# TempControl_V2_0.net
KiCad netlist of a schematic drawn in EAGLE
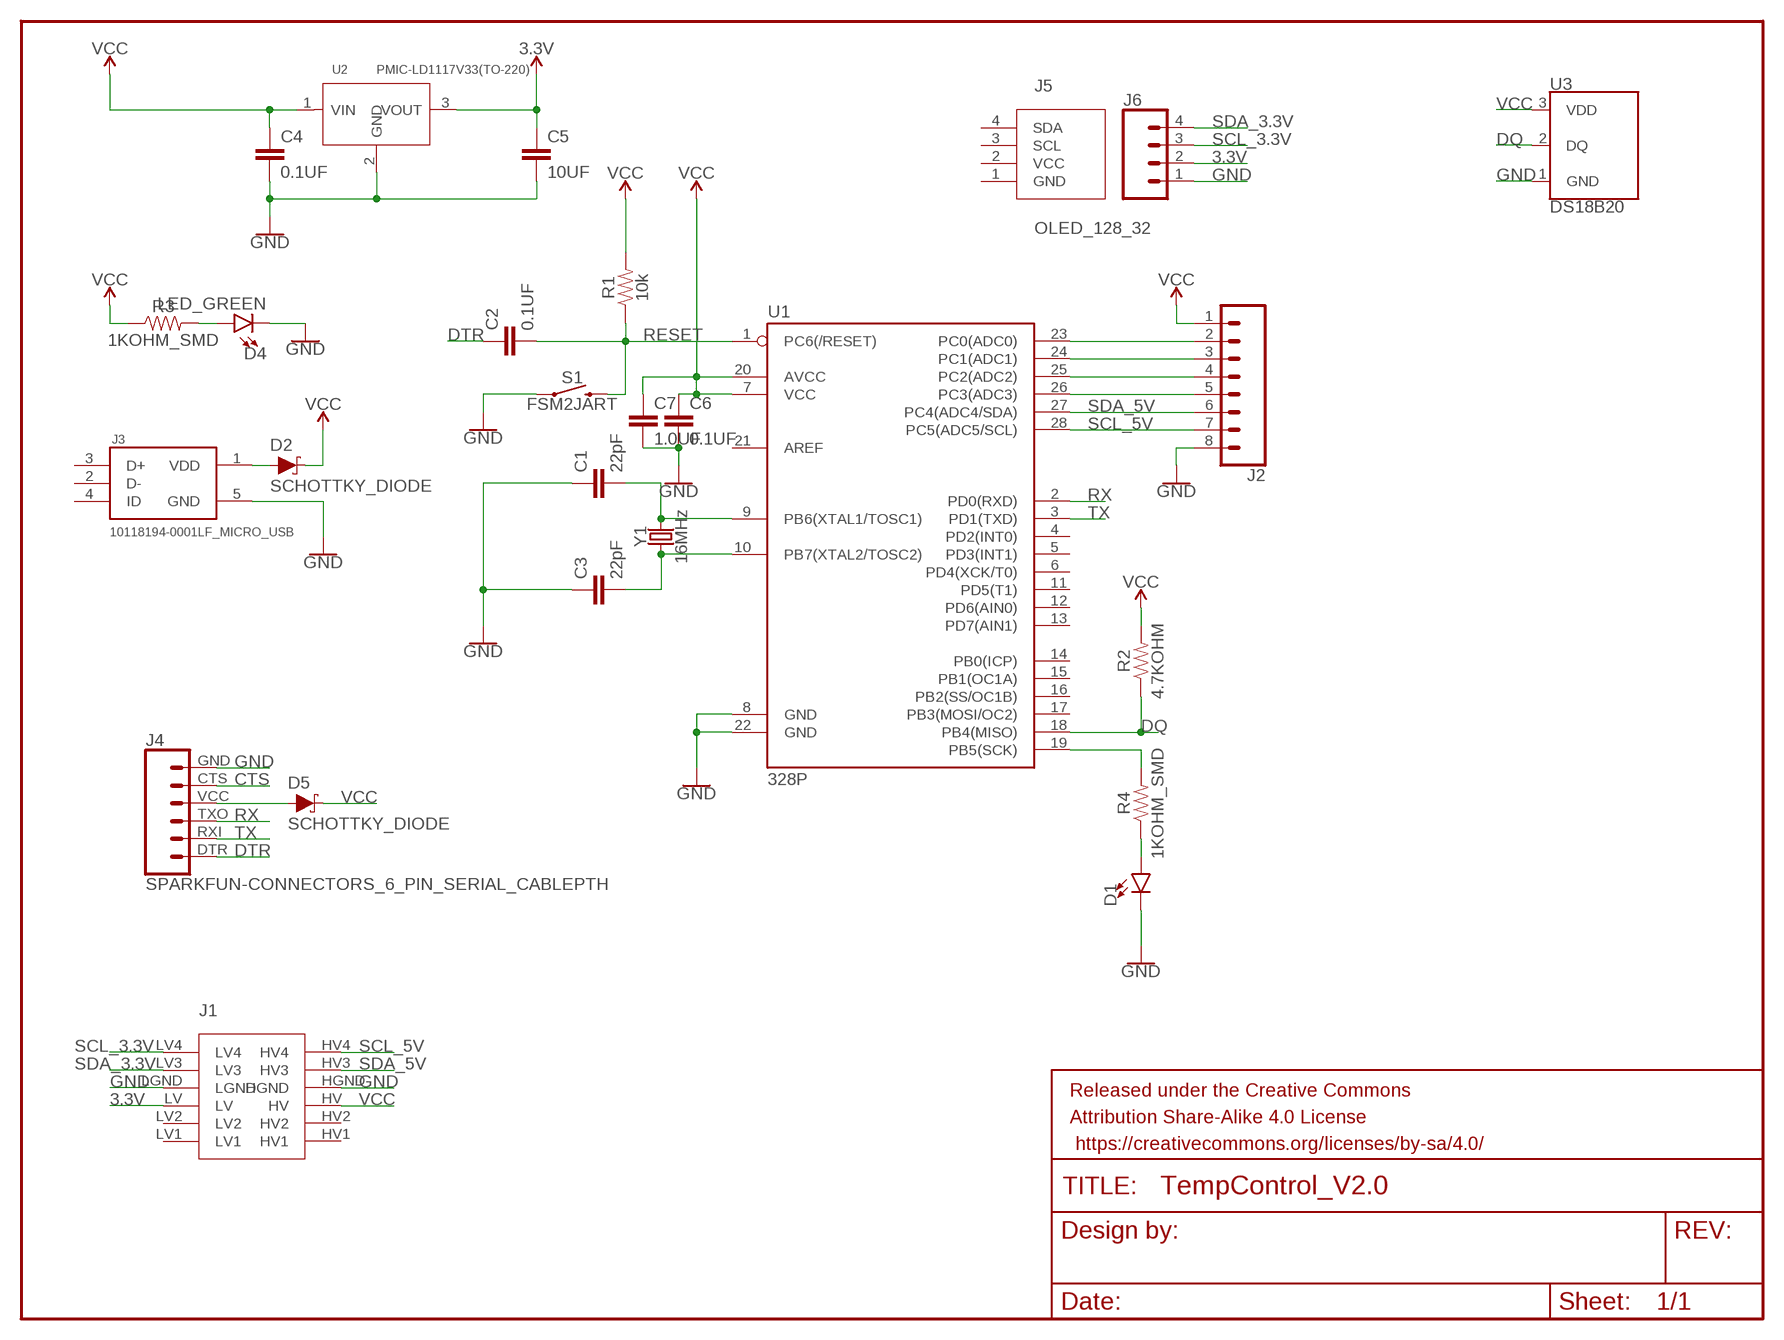
[diagram p0: schematic, sheet 1]

(export (version "E")
  (design (tool "Eeschema 10.0.6"))
  (components
    (comp (ref "C1")
      (value "22pF")
      (footprint "eagle-import:CAP-PTH-2.54")
      (libsource (lib "eagle-import") (part "22PF-PTH-2.54MM-200V-5%"))
    )
    (comp (ref "C2")
      (value "0.1UF")
      (footprint "eagle-import:CAP-PTH-2.54")
      (libsource (lib "eagle-import") (part "0.1UF"))
    )
    (comp (ref "C3")
      (value "22pF")
      (footprint "eagle-import:CAP-PTH-2.54")
      (libsource (lib "eagle-import") (part "22PF-PTH-2.54MM-200V-5%"))
    )
    (comp (ref "C4")
      (value "0.1UF")
      (footprint "eagle-import:CAP-PTH-2.54")
      (libsource (lib "eagle-import") (part "0.1UF"))
    )
    (comp (ref "C5")
      (value "10UF")
      (footprint "eagle-import:CAP-PTH-5MM")
      (libsource (lib "eagle-import") (part "10UF"))
    )
    (comp (ref "C6")
      (value "0.1UF")
      (footprint "eagle-import:CAP-PTH-2.54")
      (libsource (lib "eagle-import") (part "0.1UF"))
    )
    (comp (ref "C7")
      (value "1.0UF")
      (footprint "eagle-import:CAP-PTH-5MM")
      (libsource (lib "eagle-import") (part "1.0UF"))
    )
    (comp (ref "D1")
      (value "LED_RED5MM")
      (footprint "eagle-import:LED_5MM")
      (libsource (lib "eagle-import") (part "LED_RED5MM"))
    )
    (comp (ref "D2")
      (value "SCHOTTKY_DIODE")
      (footprint "eagle-import:DIODE_0805")
      (libsource (lib "eagle-import") (part "SCHOTTKY_DIODE"))
    )
    (comp (ref "D4")
      (value "LED_GREEN")
      (footprint "eagle-import:LED-0603")
      (libsource (lib "eagle-import") (part "LED_GREEN"))
    )
    (comp (ref "D5")
      (value "SCHOTTKY_DIODE")
      (footprint "eagle-import:DIODE_0805")
      (libsource (lib "eagle-import") (part "SCHOTTKY_DIODE"))
    )
    (comp (ref "FRAME1")
      (value "FRAME-LETTERNO_PACKAGE")
      (footprint "eagle-import:DUMMY")
      (fields (field (name "DESIGNER") "Nobody"))
      (libsource (lib "eagle-import") (part "FRAME-LETTERNO_PACKAGE"))
    )
    (comp (ref "J1")
      (value "LEVEL_SHIFTER")
      (footprint "eagle-import:LEVEL_SHIFTER")
      (libsource (lib "eagle-import") (part "LEVEL_SHIFTER"))
    )
    (comp (ref "J2")
      (value "SPARKFUN-CONNECTORS_CONN_08\"")
      (footprint "eagle-import:SPARKFUN-CONNECTORS_1X08")
      (libsource (lib "eagle-import") (part "SPARKFUN-CONNECTORS_CONN_08{dblquote}"))
    )
    (comp (ref "J3")
      (value "10118194-0001LF_MICRO_USB")
      (footprint "eagle-import:FRAMATOME_10118194-0001LF")
      (fields (field (name "MF") "Amphenol") (field (name "MP") "10118194-0001LF"))
      (libsource (lib "eagle-import") (part "10118194-0001LF_MICRO_USB"))
    )
    (comp (ref "J4")
      (value "SPARKFUN-CONNECTORS_6_PIN_SERIAL_CABLEPTH")
      (footprint "eagle-import:SPARKFUN-CONNECTORS_FTDI_BASIC")
      (libsource (lib "eagle-import") (part "SPARKFUN-CONNECTORS_6_PIN_SERIAL_CABLEPTH"))
    )
    (comp (ref "J5")
      (value "OLED_128_32")
      (footprint "eagle-import:OLED_128_32")
      (libsource (lib "eagle-import") (part "OLED_128_32"))
    )
    (comp (ref "J6")
      (value "CONN_04")
      (footprint "eagle-import:1X04")
      (libsource (lib "eagle-import") (part "CONN_04"))
    )
    (comp (ref "R1")
      (value "10k")
      (footprint "eagle-import:AXIAL-0.3")
      (libsource (lib "eagle-import") (part "10KOHM-HORIZ-1/4W-1%"))
    )
    (comp (ref "R2")
      (value "4.7KOHM")
      (footprint "eagle-import:AXIAL-0.3")
      (libsource (lib "eagle-import") (part "4.7KOHM"))
    )
    (comp (ref "R3")
      (value "1KOHM_SMD")
      (footprint "eagle-import:0603")
      (libsource (lib "eagle-import") (part "1KOHM_SMD"))
    )
    (comp (ref "R4")
      (value "1KOHM_SMD")
      (footprint "eagle-import:0603")
      (libsource (lib "eagle-import") (part "1KOHM_SMD"))
    )
    (comp (ref "S1")
      (value "FSM2JART")
      (footprint "eagle-import:FSM2JART")
      (libsource (lib "eagle-import") (part "FSM2JART"))
    )
    (comp (ref "U1")
      (value "328P")
      (footprint "eagle-import:DIP28")
      (libsource (lib "eagle-import") (part "ATMEGA328P_PDIP"))
    )
    (comp (ref "U2")
      (value "PMIC-LD1117V33(TO-220)")
      (footprint "eagle-import:TO-220")
      (fields (field (name "MF") "STMicroelectronics") (field (name "MP") "LD1117V33"))
      (libsource (lib "eagle-import") (part "PMIC-LD1117V33(TO-220)"))
    )
    (comp (ref "U3")
      (value "DS18B20")
      (footprint "eagle-import:TO-92-AMMO")
      (libsource (lib "eagle-import") (part "DS18B20"))
    )
    (comp (ref "Y1")
      (value "16MHz")
      (footprint "eagle-import:HC49US")
      (libsource (lib "eagle-import") (part "CRYSTAL-16MHZPTH-HC49US"))
    )
  )
  (nets
    (net (code "1") (name "/CTS") (class "Default")
      (node (ref "J4") (pin "CTS") (pinfunction "5_CTS") (pintype "passive"))
    )
    (net (code "2") (name "/DQ") (class "Default")
      (node (ref "R2") (pin "P$1") (pinfunction "1_P$1") (pintype "passive"))
      (node (ref "U1") (pin "18") (pinfunction "PB4(MISO)_18") (pintype "bidirectional"))
      (node (ref "U3") (pin "2") (pinfunction "DQ_2") (pintype "bidirectional"))
    )
    (net (code "3") (name "/DTR") (class "Default")
      (node (ref "C2") (pin "1") (pinfunction "1_1") (pintype "passive"))
      (node (ref "J4") (pin "DTR") (pinfunction "1_DTR") (pintype "passive"))
    )
    (net (code "4") (name "/RESET") (class "Default")
      (node (ref "C2") (pin "2") (pinfunction "2_2") (pintype "passive"))
      (node (ref "R1") (pin "P$1") (pinfunction "1_P$1") (pintype "passive"))
      (node (ref "S1") (pin "2") (pinfunction "2_2") (pintype "passive"))
      (node (ref "U1") (pin "1") (pinfunction "PC6(/RESET)_1") (pintype "bidirectional"))
    )
    (net (code "5") (name "/RX") (class "Default")
      (node (ref "J4") (pin "TXO") (pinfunction "3_TXO") (pintype "passive"))
      (node (ref "U1") (pin "2") (pinfunction "PD0(RXD)_2") (pintype "bidirectional"))
    )
    (net (code "6") (name "/SCL_3.3V") (class "Default")
      (node (ref "J1") (pin "LV4") (pinfunction "LV4_LV4") (pintype "bidirectional"))
      (node (ref "J6") (pin "3") (pinfunction "3_3") (pintype "passive"))
    )
    (net (code "7") (name "/SCL_5V") (class "Default")
      (node (ref "J1") (pin "HV4") (pinfunction "HV4_HV4") (pintype "bidirectional"))
      (node (ref "J2") (pin "7") (pinfunction "7_7") (pintype "passive"))
      (node (ref "U1") (pin "28") (pinfunction "PC5(ADC5/SCL)_28") (pintype "bidirectional"))
    )
    (net (code "8") (name "/SDA_3.3V") (class "Default")
      (node (ref "J1") (pin "LV3") (pinfunction "LV3_LV3") (pintype "bidirectional"))
      (node (ref "J6") (pin "4") (pinfunction "4_4") (pintype "passive"))
    )
    (net (code "9") (name "/SDA_5V") (class "Default")
      (node (ref "J1") (pin "HV3") (pinfunction "HV3_HV3") (pintype "bidirectional"))
      (node (ref "J2") (pin "6") (pinfunction "6_6") (pintype "passive"))
      (node (ref "U1") (pin "27") (pinfunction "PC4(ADC4/SDA)_27") (pintype "bidirectional"))
    )
    (net (code "10") (name "/TX") (class "Default")
      (node (ref "J4") (pin "RXI") (pinfunction "2_RXI") (pintype "passive"))
      (node (ref "U1") (pin "3") (pinfunction "PD1(TXD)_3") (pintype "bidirectional"))
    )
    (net (code "11") (name "3.3V") (class "Default")
      (node (ref "C5") (pin "1") (pinfunction "1_1") (pintype "passive"))
      (node (ref "J1") (pin "LV") (pinfunction "LV_LV") (pintype "bidirectional"))
      (node (ref "J6") (pin "2") (pinfunction "2_2") (pintype "passive"))
      (node (ref "U2") (pin "3") (pinfunction "VOUT_3") (pintype "bidirectional"))
    )
    (net (code "12") (name "GND") (class "Default")
      (node (ref "C1") (pin "1") (pinfunction "1_1") (pintype "passive"))
      (node (ref "C3") (pin "1") (pinfunction "1_1") (pintype "passive"))
      (node (ref "C4") (pin "2") (pinfunction "2_2") (pintype "passive"))
      (node (ref "C5") (pin "2") (pinfunction "2_2") (pintype "passive"))
      (node (ref "C6") (pin "2") (pinfunction "2_2") (pintype "passive"))
      (node (ref "C7") (pin "2") (pinfunction "2_2") (pintype "passive"))
      (node (ref "D1") (pin "K") (pinfunction "2_K") (pintype "passive"))
      (node (ref "D4") (pin "2") (pinfunction "2_2") (pintype "passive"))
      (node (ref "J1") (pin "HGND") (pinfunction "HGND_HGND") (pintype "bidirectional"))
      (node (ref "J1") (pin "LGND") (pinfunction "LGND_LGND") (pintype "bidirectional"))
      (node (ref "J2") (pin "8") (pinfunction "8_8") (pintype "passive"))
      (node (ref "J3") (pin "5") (pinfunction "GND_5") (pintype "power_in"))
      (node (ref "J4") (pin "GND") (pinfunction "6_GND") (pintype "passive"))
      (node (ref "J6") (pin "1") (pinfunction "1_1") (pintype "passive"))
      (node (ref "S1") (pin "1") (pinfunction "1_1") (pintype "passive"))
      (node (ref "U1") (pin "22") (pinfunction "GND_22") (pintype "bidirectional"))
      (node (ref "U1") (pin "8") (pinfunction "GND_8") (pintype "bidirectional"))
      (node (ref "U2") (pin "2") (pinfunction "GND_2") (pintype "bidirectional"))
      (node (ref "U3") (pin "1") (pinfunction "GND_1") (pintype "power_in"))
    )
    (net (code "13") (name "Net-(D1-1)") (class "Default")
      (node (ref "D1") (pin "A") (pinfunction "1_A") (pintype "passive"))
      (node (ref "R4") (pin "1") (pinfunction "1_1") (pintype "passive"))
    )
    (net (code "14") (name "Net-(D4-Pad1)") (class "Default")
      (node (ref "D4") (pin "1") (pinfunction "1_1") (pintype "passive"))
      (node (ref "R3") (pin "2") (pinfunction "2_2") (pintype "passive"))
    )
    (net (code "15") (name "Net-(J3-VDD)") (class "Default")
      (node (ref "D2") (pin "1") (pinfunction "1_1") (pintype "passive"))
      (node (ref "J3") (pin "1") (pinfunction "VDD_1") (pintype "power_in"))
    )
    (net (code "16") (name "Net-(J4-4)") (class "Default")
      (node (ref "D5") (pin "1") (pinfunction "1_1") (pintype "passive"))
      (node (ref "J4") (pin "VCC") (pinfunction "4_VCC") (pintype "passive"))
    )
    (net (code "17") (name "Net-(U1-PB5(SCK))") (class "Default")
      (node (ref "R4") (pin "2") (pinfunction "2_2") (pintype "passive"))
      (node (ref "U1") (pin "19") (pinfunction "PB5(SCK)_19") (pintype "bidirectional"))
    )
    (net (code "18") (name "Net-(U1-PB6(XTAL1{slash}TOSC1))") (class "Default")
      (node (ref "C1") (pin "2") (pinfunction "2_2") (pintype "passive"))
      (node (ref "U1") (pin "9") (pinfunction "PB6(XTAL1/TOSC1)_9") (pintype "bidirectional"))
      (node (ref "Y1") (pin "2") (pinfunction "2_2") (pintype "passive"))
    )
    (net (code "19") (name "Net-(U1-PB7(XTAL2{slash}TOSC2))") (class "Default")
      (node (ref "C3") (pin "2") (pinfunction "2_2") (pintype "passive"))
      (node (ref "U1") (pin "10") (pinfunction "PB7(XTAL2/TOSC2)_10") (pintype "bidirectional"))
      (node (ref "Y1") (pin "1") (pinfunction "1_1") (pintype "passive"))
    )
    (net (code "20") (name "Net-(U1-PC0(ADC0))") (class "Default")
      (node (ref "J2") (pin "2") (pinfunction "2_2") (pintype "passive"))
      (node (ref "U1") (pin "23") (pinfunction "PC0(ADC0)_23") (pintype "bidirectional"))
    )
    (net (code "21") (name "Net-(U1-PC1(ADC1))") (class "Default")
      (node (ref "J2") (pin "3") (pinfunction "3_3") (pintype "passive"))
      (node (ref "U1") (pin "24") (pinfunction "PC1(ADC1)_24") (pintype "bidirectional"))
    )
    (net (code "22") (name "Net-(U1-PC2(ADC2))") (class "Default")
      (node (ref "J2") (pin "4") (pinfunction "4_4") (pintype "passive"))
      (node (ref "U1") (pin "25") (pinfunction "PC2(ADC2)_25") (pintype "bidirectional"))
    )
    (net (code "23") (name "Net-(U1-PC3(ADC3))") (class "Default")
      (node (ref "J2") (pin "5") (pinfunction "5_5") (pintype "passive"))
      (node (ref "U1") (pin "26") (pinfunction "PC3(ADC3)_26") (pintype "bidirectional"))
    )
    (net (code "24") (name "VCC") (class "Default")
      (node (ref "C4") (pin "1") (pinfunction "1_1") (pintype "passive"))
      (node (ref "C6") (pin "1") (pinfunction "1_1") (pintype "passive"))
      (node (ref "C7") (pin "1") (pinfunction "1_1") (pintype "passive"))
      (node (ref "D2") (pin "2") (pinfunction "2_2") (pintype "passive"))
      (node (ref "D5") (pin "2") (pinfunction "2_2") (pintype "passive"))
      (node (ref "J1") (pin "HV") (pinfunction "HV_HV") (pintype "bidirectional"))
      (node (ref "J2") (pin "1") (pinfunction "1_1") (pintype "passive"))
      (node (ref "R1") (pin "P$2") (pinfunction "2_P$2") (pintype "passive"))
      (node (ref "R2") (pin "P$2") (pinfunction "2_P$2") (pintype "passive"))
      (node (ref "R3") (pin "1") (pinfunction "1_1") (pintype "passive"))
      (node (ref "U1") (pin "20") (pinfunction "AVCC_20") (pintype "bidirectional"))
      (node (ref "U1") (pin "7") (pinfunction "VCC_7") (pintype "bidirectional"))
      (node (ref "U2") (pin "1") (pinfunction "VIN_1") (pintype "bidirectional"))
      (node (ref "U3") (pin "3") (pinfunction "VDD_3") (pintype "power_in"))
    )
    (net (code "25") (name "unconnected-(J1-PadHV1)") (class "Default")
      (node (ref "J1") (pin "HV1") (pinfunction "HV1_HV1") (pintype "bidirectional"))
    )
    (net (code "26") (name "unconnected-(J1-PadHV2)") (class "Default")
      (node (ref "J1") (pin "HV2") (pinfunction "HV2_HV2") (pintype "bidirectional"))
    )
    (net (code "27") (name "unconnected-(J1-PadLV1)") (class "Default")
      (node (ref "J1") (pin "LV1") (pinfunction "LV1_LV1") (pintype "bidirectional"))
    )
    (net (code "28") (name "unconnected-(J1-PadLV2)") (class "Default")
      (node (ref "J1") (pin "LV2") (pinfunction "LV2_LV2") (pintype "bidirectional"))
    )
    (net (code "29") (name "unconnected-(J3-D+-Pad3)") (class "Default")
      (node (ref "J3") (pin "3") (pinfunction "D+_3") (pintype "bidirectional"))
    )
    (net (code "30") (name "unconnected-(J3-D--Pad2)") (class "Default")
      (node (ref "J3") (pin "2") (pinfunction "D-_2") (pintype "bidirectional"))
    )
    (net (code "31") (name "unconnected-(J3-ID-Pad4)") (class "Default")
      (node (ref "J3") (pin "4") (pinfunction "ID_4") (pintype "passive"))
    )
    (net (code "32") (name "unconnected-(J5-GND-Pad1)") (class "Default")
      (node (ref "J5") (pin "1") (pinfunction "GND_1") (pintype "bidirectional"))
    )
    (net (code "33") (name "unconnected-(J5-SCL-Pad3)") (class "Default")
      (node (ref "J5") (pin "3") (pinfunction "SCL_3") (pintype "bidirectional"))
    )
    (net (code "34") (name "unconnected-(J5-SDA-Pad4)") (class "Default")
      (node (ref "J5") (pin "4") (pinfunction "SDA_4") (pintype "bidirectional"))
    )
    (net (code "35") (name "unconnected-(J5-VCC-Pad2)") (class "Default")
      (node (ref "J5") (pin "2") (pinfunction "VCC_2") (pintype "bidirectional"))
    )
    (net (code "36") (name "unconnected-(U1-AREF-Pad21)") (class "Default")
      (node (ref "U1") (pin "21") (pinfunction "AREF_21") (pintype "bidirectional"))
    )
    (net (code "37") (name "unconnected-(U1-PB0(ICP)-Pad14)") (class "Default")
      (node (ref "U1") (pin "14") (pinfunction "PB0(ICP)_14") (pintype "bidirectional"))
    )
    (net (code "38") (name "unconnected-(U1-PB1(OC1A)-Pad15)") (class "Default")
      (node (ref "U1") (pin "15") (pinfunction "PB1(OC1A)_15") (pintype "bidirectional"))
    )
    (net (code "39") (name "unconnected-(U1-PB2(SS{slash}OC1B)-Pad16)") (class "Default")
      (node (ref "U1") (pin "16") (pinfunction "PB2(SS/OC1B)_16") (pintype "bidirectional"))
    )
    (net (code "40") (name "unconnected-(U1-PB3(MOSI{slash}OC2)-Pad17)") (class "Default")
      (node (ref "U1") (pin "17") (pinfunction "PB3(MOSI/OC2)_17") (pintype "bidirectional"))
    )
    (net (code "41") (name "unconnected-(U1-PD2(INT0)-Pad4)") (class "Default")
      (node (ref "U1") (pin "4") (pinfunction "PD2(INT0)_4") (pintype "bidirectional"))
    )
    (net (code "42") (name "unconnected-(U1-PD3(INT1)-Pad5)") (class "Default")
      (node (ref "U1") (pin "5") (pinfunction "PD3(INT1)_5") (pintype "bidirectional"))
    )
    (net (code "43") (name "unconnected-(U1-PD4(XCK{slash}T0)-Pad6)") (class "Default")
      (node (ref "U1") (pin "6") (pinfunction "PD4(XCK/T0)_6") (pintype "bidirectional"))
    )
    (net (code "44") (name "unconnected-(U1-PD5(T1)-Pad11)") (class "Default")
      (node (ref "U1") (pin "11") (pinfunction "PD5(T1)_11") (pintype "bidirectional"))
    )
    (net (code "45") (name "unconnected-(U1-PD6(AIN0)-Pad12)") (class "Default")
      (node (ref "U1") (pin "12") (pinfunction "PD6(AIN0)_12") (pintype "bidirectional"))
    )
    (net (code "46") (name "unconnected-(U1-PD7(AIN1)-Pad13)") (class "Default")
      (node (ref "U1") (pin "13") (pinfunction "PD7(AIN1)_13") (pintype "bidirectional"))
    )
  )
)
